# NU-SYNTHS_MIDICV.net
KiCad netlist of a schematic drawn in Altium Designer
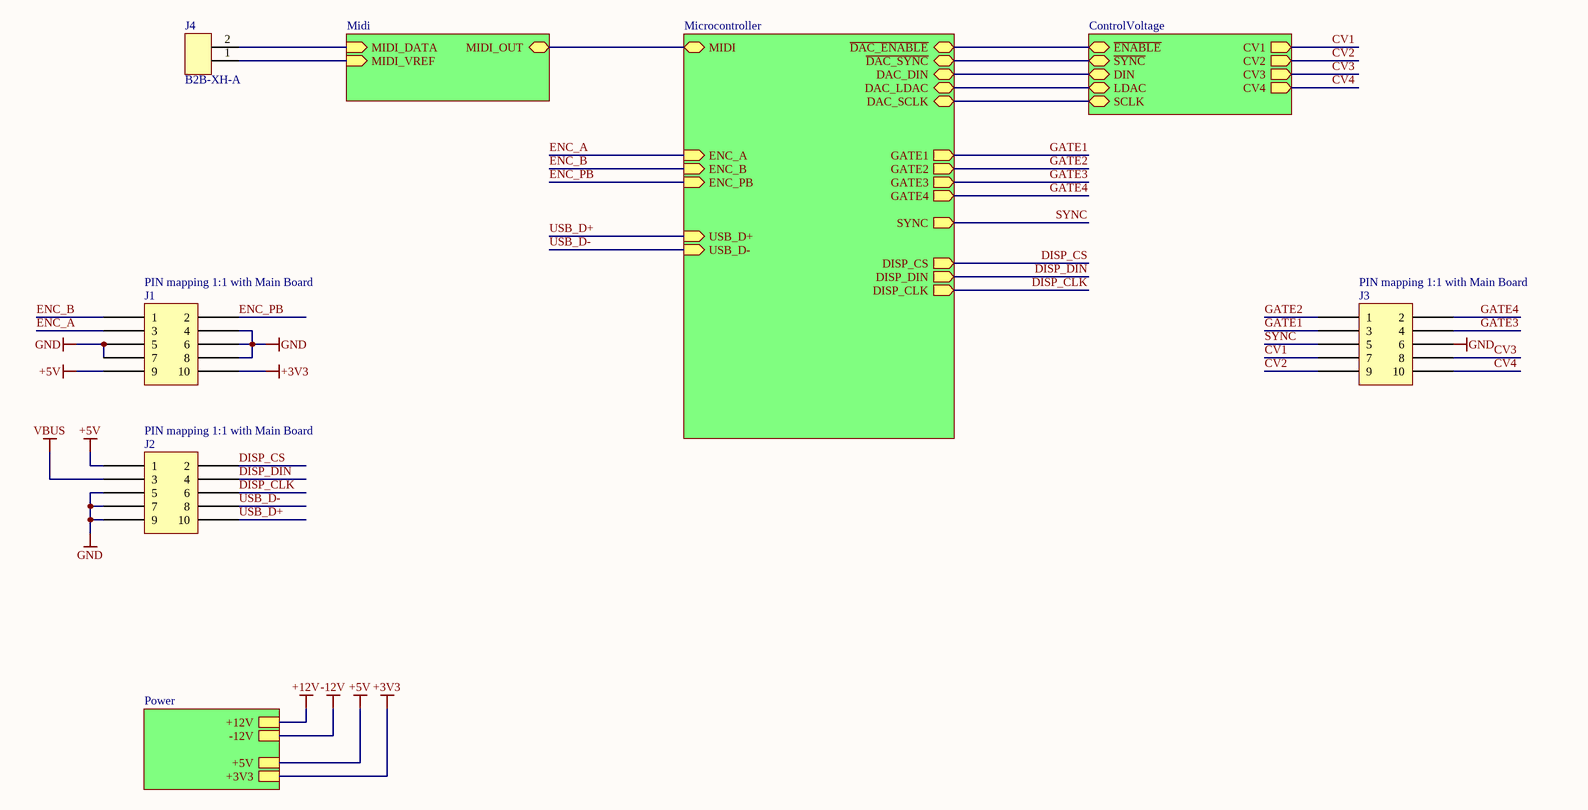
[diagram p0: NU-SYNTHS_MIDICV.SchDoc]

(export (version "E")
  (design (tool "Eeschema 10.0.6"))
  (components
    (comp (ref "J1")
      (value "GENERIC_HEADER_2x5")
      (footprint "HEADER_2x5_SMD_FEMALE")
      (description "Generic 2x5 header")
      (libsource (lib "LabratsSynthLib") (part "GENERIC_HEADER_2x5"))
    )
    (comp (ref "J2")
      (value "GENERIC_HEADER_2x5")
      (footprint "HEADER_2x5_SMD_FEMALE")
      (description "Generic 2x5 header")
      (libsource (lib "LabratsSynthLib") (part "GENERIC_HEADER_2x5"))
    )
    (comp (ref "J3")
      (value "GENERIC_HEADER_2x5")
      (footprint "HEADER_2x5_SMD_FEMALE")
      (description "Generic 2x5 header")
      (libsource (lib "LabratsSynthLib") (part "GENERIC_HEADER_2x5"))
    )
    (comp (ref "J4")
      (value "B2B-XH-A")
      (footprint "JST_HEADER_1x2_SMD_MALE")
      (description "Connector Header Through Hole 2 position 0.098 (2.50mm)")
      (fields (field (name "MF") "JST Sales") (field (name "MP") "B2B-XH-A(LF)(SN)"))
      (libsource (lib "LabratsSynthLib") (part "B2B-XH-A(LF)(SN)"))
    )
  )
  (nets
    (net (code "1") (name "+3V3") (class "Default")
      (node (ref "J1") (pin "10") (pinfunction "10_10") (pintype "passive"))
    )
    (net (code "2") (name "+5V") (class "Default")
      (node (ref "J1") (pin "9") (pinfunction "9_9") (pintype "passive"))
      (node (ref "J2") (pin "1") (pinfunction "1_1") (pintype "passive"))
    )
    (net (code "5") (name "/CV1") (class "Default")
      (node (ref "J3") (pin "7") (pinfunction "7_7") (pintype "passive"))
    )
    (net (code "6") (name "/CV2") (class "Default")
      (node (ref "J3") (pin "9") (pinfunction "9_9") (pintype "passive"))
    )
    (net (code "7") (name "/CV3") (class "Default")
      (node (ref "J3") (pin "8") (pinfunction "8_8") (pintype "passive"))
    )
    (net (code "8") (name "/CV4") (class "Default")
      (node (ref "J3") (pin "10") (pinfunction "10_10") (pintype "passive"))
    )
    (net (code "12") (name "/DISP_CLK") (class "Default")
      (node (ref "J2") (pin "6") (pinfunction "6_6") (pintype "passive"))
    )
    (net (code "13") (name "/DISP_CS") (class "Default")
      (node (ref "J2") (pin "2") (pinfunction "2_2") (pintype "passive"))
    )
    (net (code "14") (name "/DISP_DIN") (class "Default")
      (node (ref "J2") (pin "4") (pinfunction "4_4") (pintype "passive"))
    )
    (net (code "15") (name "/ENC_A") (class "Default")
      (node (ref "J1") (pin "3") (pinfunction "3_3") (pintype "passive"))
    )
    (net (code "16") (name "/ENC_B") (class "Default")
      (node (ref "J1") (pin "1") (pinfunction "1_1") (pintype "passive"))
    )
    (net (code "17") (name "/ENC_PB") (class "Default")
      (node (ref "J1") (pin "2") (pinfunction "2_2") (pintype "passive"))
    )
    (net (code "18") (name "/GATE1") (class "Default")
      (node (ref "J3") (pin "3") (pinfunction "3_3") (pintype "passive"))
    )
    (net (code "19") (name "/GATE2") (class "Default")
      (node (ref "J3") (pin "1") (pinfunction "1_1") (pintype "passive"))
    )
    (net (code "20") (name "/GATE3") (class "Default")
      (node (ref "J3") (pin "4") (pinfunction "4_4") (pintype "passive"))
    )
    (net (code "21") (name "/GATE4") (class "Default")
      (node (ref "J3") (pin "2") (pinfunction "2_2") (pintype "passive"))
    )
    (net (code "23") (name "/MIDI_DATA") (class "Default")
      (node (ref "J4") (pin "2") (pinfunction "2_2") (pintype "passive"))
    )
    (net (code "24") (name "/MIDI_VREF") (class "Default")
      (node (ref "J4") (pin "1") (pinfunction "1_1") (pintype "passive"))
    )
    (net (code "25") (name "/SYNC") (class "Default")
      (node (ref "J3") (pin "5") (pinfunction "5_5") (pintype "passive"))
    )
    (net (code "26") (name "/USB_D+") (class "Default")
      (node (ref "J2") (pin "10") (pinfunction "10_10") (pintype "passive"))
    )
    (net (code "27") (name "/USB_D-") (class "Default")
      (node (ref "J2") (pin "8") (pinfunction "8_8") (pintype "passive"))
    )
    (net (code "30") (name "GND") (class "Default")
      (node (ref "J1") (pin "4") (pinfunction "4_4") (pintype "passive"))
      (node (ref "J1") (pin "5") (pinfunction "5_5") (pintype "passive"))
      (node (ref "J1") (pin "6") (pinfunction "6_6") (pintype "passive"))
      (node (ref "J1") (pin "7") (pinfunction "7_7") (pintype "passive"))
      (node (ref "J1") (pin "8") (pinfunction "8_8") (pintype "passive"))
      (node (ref "J2") (pin "5") (pinfunction "5_5") (pintype "passive"))
      (node (ref "J2") (pin "7") (pinfunction "7_7") (pintype "passive"))
      (node (ref "J2") (pin "9") (pinfunction "9_9") (pintype "passive"))
      (node (ref "J3") (pin "6") (pinfunction "6_6") (pintype "passive"))
    )
    (net (code "31") (name "VBUS") (class "Default")
      (node (ref "J2") (pin "3") (pinfunction "3_3") (pintype "passive"))
    )
  )
)
